# DRONE_PI_SENSOR_BOARD.net
KiCad netlist of a schematic drawn in EasyEDA
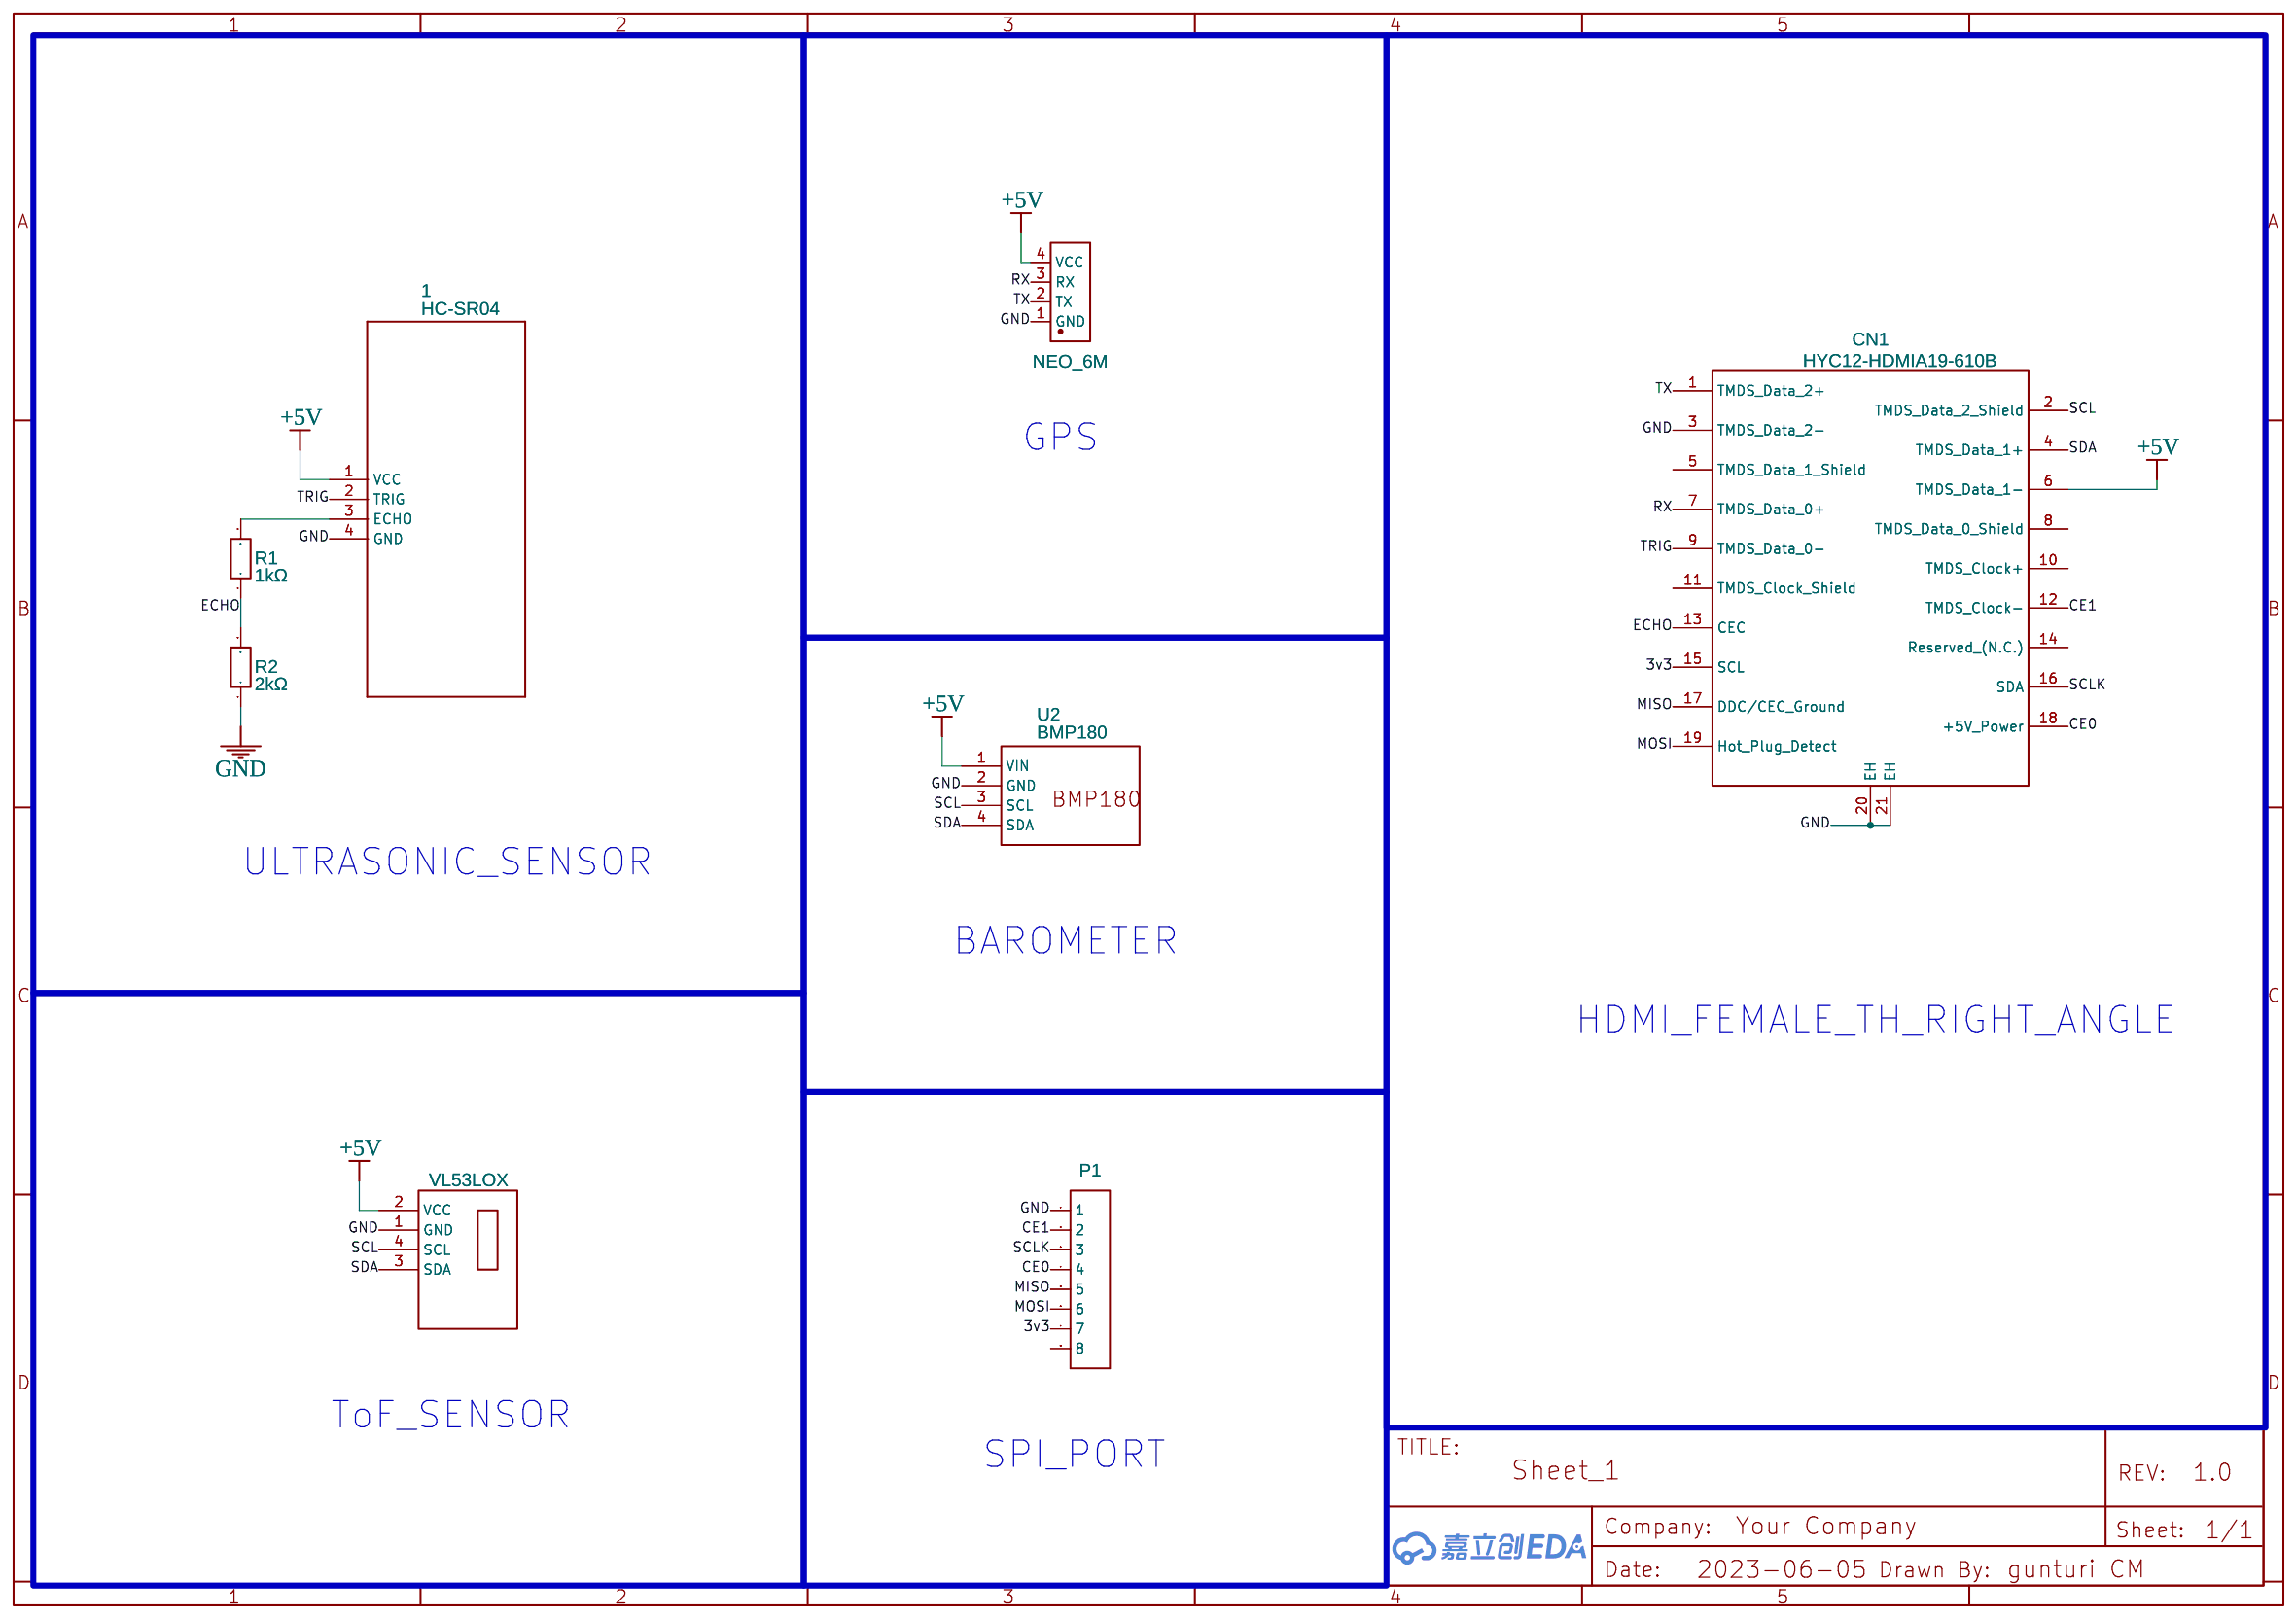
[diagram p0: schematic sheet]

(export (version "E")
  (design (tool "Eeschema 10.0.6"))
  (components
    (comp (ref "1") (value "HC-SR04") (libsource (lib "") (part "ULTRASONIC-HC-SR04 COPY")))
    (comp (ref "CN1")
      (value "HYC12-HDMIA19-610B")
      (fields (field (name "BOM_Supplier Part") "C711354"))
      (libsource (lib "") (part "HYC12-HDMIA19-610B"))
    )
    (comp (ref "NEO_6M")
      (value "XHB2.54-4P")
      (fields (field (name "BOM_Supplier Part") "C9900014704"))
      (libsource (lib "") (part "XHB2.54-4P"))
    )
    (comp (ref "P1")
      (value "HDR")
      (fields
        (field (name "BOM_Manufacturer Part") "Female headerHDR1X8-2.54")
        (field (name "BOM_Supplier Part") "C27438")
      )
      (libsource (lib "") (part "TFT 1.8. HEADER-FEMALE CONNECTOR 8PIN"))
    )
    (comp (ref "R1")
      (value "1kΩ")
      (fields
        (field (name "BOM_Manufacturer Part") "MO1/4W-220K±5%-ST52")
        (field (name "BOM_Supplier Part") "C2857428")
      )
      (libsource (lib "") (part "MO1/4W-220K±5%-ST52"))
    )
    (comp (ref "R2")
      (value "2kΩ")
      (fields
        (field (name "BOM_Manufacturer Part") "MO1/4W-220K±5%-ST52")
        (field (name "BOM_Supplier Part") "C2857428")
      )
      (libsource (lib "") (part "MO1/4W-220K±5%-ST52"))
    )
    (comp (ref "U2") (value "BMP180") (libsource (lib "") (part "BMP180")))
    (comp (ref "VL53LOX") (value "VL53LOX module SN") (libsource (lib "") (part "VL53LOX module SN")))
  )
  (nets
    (net (code "1") (name "+5V") (class "Default")
      (node (ref "1") (pin "1") (pinfunction "VCC_1") (pintype "bidirectional"))
      (node (ref "CN1") (pin "6") (pinfunction "TMDS_Data_1-_6") (pintype "unspecified"))
      (node (ref "NEO_6M") (pin "4") (pinfunction "VCC_4") (pintype "unspecified"))
      (node (ref "U2") (pin "1") (pinfunction "VIN_1") (pintype "unspecified"))
      (node (ref "VL53LOX") (pin "2") (pinfunction "VCC_2") (pintype "unspecified"))
    )
    (net (code "2") (name "/3v3") (class "Default")
      (node (ref "CN1") (pin "15") (pinfunction "SCL_15") (pintype "unspecified"))
      (node (ref "P1") (pin "7") (pinfunction "7_7") (pintype "input"))
    )
    (net (code "3") (name "/CE0") (class "Default")
      (node (ref "CN1") (pin "18") (pinfunction "+5V_Power_18") (pintype "unspecified"))
      (node (ref "P1") (pin "4") (pinfunction "4_4") (pintype "input"))
    )
    (net (code "4") (name "/CE1") (class "Default")
      (node (ref "CN1") (pin "12") (pinfunction "TMDS_Clock-_12") (pintype "unspecified"))
      (node (ref "P1") (pin "2") (pinfunction "2_2") (pintype "input"))
    )
    (net (code "5") (name "/ECHO") (class "Default")
      (node (ref "CN1") (pin "13") (pinfunction "CEC_13") (pintype "unspecified"))
      (node (ref "R1") (pin "1") (pinfunction "1_1") (pintype "unspecified"))
      (node (ref "R2") (pin "2") (pinfunction "2_2") (pintype "unspecified"))
    )
    (net (code "6") (name "/MISO") (class "Default")
      (node (ref "CN1") (pin "17") (pinfunction "DDC/CEC_Ground_17") (pintype "unspecified"))
      (node (ref "P1") (pin "5") (pinfunction "5_5") (pintype "input"))
    )
    (net (code "7") (name "/MOSI") (class "Default")
      (node (ref "CN1") (pin "19") (pinfunction "Hot_Plug_Detect_19") (pintype "unspecified"))
      (node (ref "P1") (pin "6") (pinfunction "6_6") (pintype "input"))
    )
    (net (code "8") (name "/RX") (class "Default")
      (node (ref "CN1") (pin "7") (pinfunction "TMDS_Data_0+_7") (pintype "unspecified"))
      (node (ref "NEO_6M") (pin "3") (pinfunction "RX_3") (pintype "unspecified"))
    )
    (net (code "9") (name "/SCL") (class "Default")
      (node (ref "CN1") (pin "2") (pinfunction "TMDS_Data_2_Shield_2") (pintype "unspecified"))
      (node (ref "U2") (pin "3") (pinfunction "SCL_3") (pintype "unspecified"))
      (node (ref "VL53LOX") (pin "4") (pinfunction "SCL_4") (pintype "unspecified"))
    )
    (net (code "10") (name "/SCLK") (class "Default")
      (node (ref "CN1") (pin "16") (pinfunction "SDA_16") (pintype "unspecified"))
      (node (ref "P1") (pin "3") (pinfunction "3_3") (pintype "input"))
    )
    (net (code "11") (name "/SDA") (class "Default")
      (node (ref "CN1") (pin "4") (pinfunction "TMDS_Data_1+_4") (pintype "unspecified"))
      (node (ref "U2") (pin "4") (pinfunction "SDA_4") (pintype "unspecified"))
      (node (ref "VL53LOX") (pin "3") (pinfunction "SDA_3") (pintype "unspecified"))
    )
    (net (code "12") (name "/TRIG") (class "Default")
      (node (ref "1") (pin "2") (pinfunction "TRIG_2") (pintype "bidirectional"))
      (node (ref "CN1") (pin "9") (pinfunction "TMDS_Data_0-_9") (pintype "unspecified"))
    )
    (net (code "13") (name "/TX") (class "Default")
      (node (ref "CN1") (pin "1") (pinfunction "TMDS_Data_2+_1") (pintype "unspecified"))
      (node (ref "NEO_6M") (pin "2") (pinfunction "TX_2") (pintype "unspecified"))
    )
    (net (code "14") (name "GND") (class "Default")
      (node (ref "1") (pin "4") (pinfunction "GND_4") (pintype "bidirectional"))
      (node (ref "CN1") (pin "20") (pinfunction "EH_20") (pintype "unspecified"))
      (node (ref "CN1") (pin "21") (pinfunction "EH_21") (pintype "unspecified"))
      (node (ref "CN1") (pin "3") (pinfunction "TMDS_Data_2-_3") (pintype "unspecified"))
      (node (ref "NEO_6M") (pin "1") (pinfunction "GND_1") (pintype "unspecified"))
      (node (ref "P1") (pin "1") (pinfunction "1_1") (pintype "input"))
      (node (ref "R2") (pin "1") (pinfunction "1_1") (pintype "unspecified"))
      (node (ref "U2") (pin "2") (pinfunction "GND_2") (pintype "unspecified"))
      (node (ref "VL53LOX") (pin "1") (pinfunction "GND_1") (pintype "unspecified"))
    )
    (net (code "15") (name "Net-(1-ECHO)") (class "Default")
      (node (ref "1") (pin "3") (pinfunction "ECHO_3") (pintype "bidirectional"))
      (node (ref "R1") (pin "2") (pinfunction "2_2") (pintype "unspecified"))
    )
    (net (code "16") (name "unconnected-(CN1-Reserved_(N.C.)-Pad14)") (class "Default")
      (node (ref "CN1") (pin "14") (pinfunction "Reserved_(N.C.)_14") (pintype "unspecified"))
    )
    (net (code "17") (name "unconnected-(CN1-TMDS_Clock+-Pad10)") (class "Default")
      (node (ref "CN1") (pin "10") (pinfunction "TMDS_Clock+_10") (pintype "unspecified"))
    )
    (net (code "18") (name "unconnected-(CN1-TMDS_Clock_Shield-Pad11)") (class "Default")
      (node (ref "CN1") (pin "11") (pinfunction "TMDS_Clock_Shield_11") (pintype "unspecified"))
    )
    (net (code "19") (name "unconnected-(CN1-TMDS_Data_0_Shield-Pad8)") (class "Default")
      (node (ref "CN1") (pin "8") (pinfunction "TMDS_Data_0_Shield_8") (pintype "unspecified"))
    )
    (net (code "20") (name "unconnected-(CN1-TMDS_Data_1_Shield-Pad5)") (class "Default")
      (node (ref "CN1") (pin "5") (pinfunction "TMDS_Data_1_Shield_5") (pintype "unspecified"))
    )
    (net (code "21") (name "unconnected-(P1-Pad8)") (class "Default")
      (node (ref "P1") (pin "8") (pinfunction "8_8") (pintype "input"))
    )
  )
)
